# IOB-I2C-MCP23017.net
KiCad netlist of a schematic drawn in EAGLE
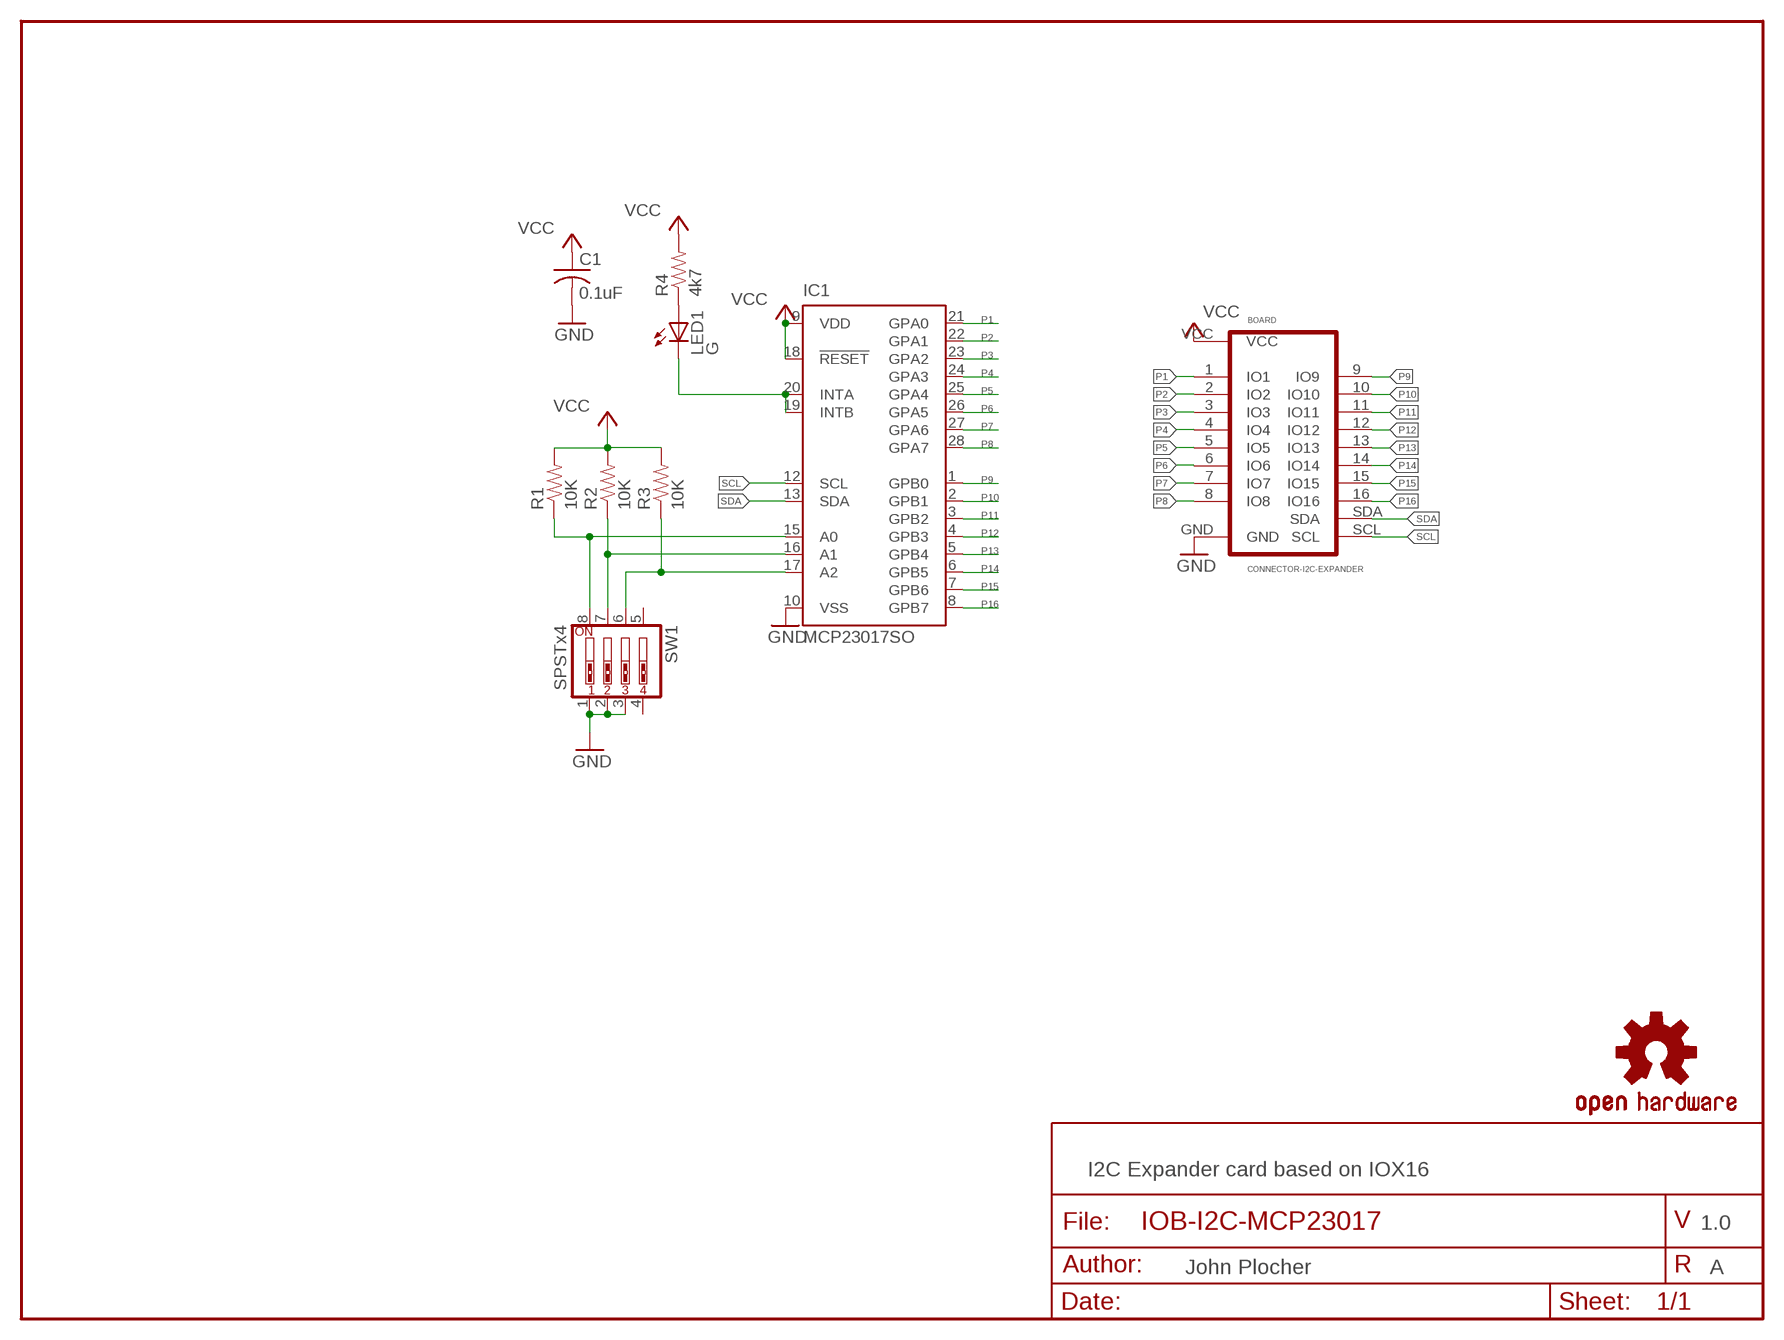
[diagram p0: schematic, sheet 1]

(export (version "E")
  (design (tool "Eeschema 10.0.6"))
  (components
    (comp (ref "BOARD")
      (value "CONNECTOR-I2C-EXPANDER")
      (footprint "eagle-import:I2C-EXPANDER")
      (libsource (lib "eagle-import") (part "CONNECTOR-I2C-EXPANDER"))
    )
    (comp (ref "C1")
      (value "0.1uF")
      (footprint "eagle-import:0603-CAP")
      (libsource (lib "eagle-import") (part "CAP0603"))
    )
    (comp (ref "IC1")
      (value "MCP23017SO")
      (footprint "eagle-import:SO28W")
      (fields (field (name "MF") "MICROCHIP") (field (name "MPN") "MCP23017-E/SO"))
      (libsource (lib "eagle-import") (part "MCP23017SO"))
    )
    (comp (ref "LED1")
      (value "G")
      (footprint "eagle-import:0603-LED")
      (libsource (lib "eagle-import") (part "LED0603-LED"))
    )
    (comp (ref "OSHW1")
      (value "OSHW")
      (footprint "eagle-import:OSHW-LOGO-M")
      (libsource (lib "eagle-import") (part "DOC-OSHW-LOGO-M"))
    )
    (comp (ref "R1")
      (value "10K")
      (footprint "eagle-import:0603-RES")
      (libsource (lib "eagle-import") (part "R0603-RES"))
    )
    (comp (ref "R2")
      (value "10K")
      (footprint "eagle-import:0603-RES")
      (libsource (lib "eagle-import") (part "R0603-RES"))
    )
    (comp (ref "R3")
      (value "10K")
      (footprint "eagle-import:0603-RES")
      (libsource (lib "eagle-import") (part "R0603-RES"))
    )
    (comp (ref "R4")
      (value "4k7")
      (footprint "eagle-import:0603-RES")
      (libsource (lib "eagle-import") (part "R0603-RES"))
    )
    (comp (ref "SW1")
      (value "SPSTx4")
      (footprint "eagle-import:EDG-04")
      (libsource (lib "eagle-import") (part "SW_DIP-4"))
    )
  )
  (nets
    (net (code "1") (name "GND") (class "Default")
      (node (ref "BOARD") (pin "GND") (pinfunction "GND_GND") (pintype "bidirectional"))
      (node (ref "C1") (pin "2") (pinfunction "2_2") (pintype "passive"))
      (node (ref "IC1") (pin "10") (pinfunction "VSS_10") (pintype "power_in"))
      (node (ref "SW1") (pin "1") (pinfunction "1_1") (pintype "passive"))
      (node (ref "SW1") (pin "2") (pinfunction "2_2") (pintype "passive"))
      (node (ref "SW1") (pin "3") (pinfunction "3_3") (pintype "passive"))
    )
    (net (code "2") (name "Net-(IC1-A0)") (class "Default")
      (node (ref "IC1") (pin "15") (pinfunction "A0_15") (pintype "input"))
      (node (ref "R1") (pin "1") (pinfunction "1_1") (pintype "passive"))
      (node (ref "SW1") (pin "8") (pinfunction "8_8") (pintype "passive"))
    )
    (net (code "3") (name "Net-(IC1-A1)") (class "Default")
      (node (ref "IC1") (pin "16") (pinfunction "A1_16") (pintype "input"))
      (node (ref "R2") (pin "1") (pinfunction "1_1") (pintype "passive"))
      (node (ref "SW1") (pin "7") (pinfunction "7_7") (pintype "passive"))
    )
    (net (code "4") (name "Net-(IC1-A2)") (class "Default")
      (node (ref "IC1") (pin "17") (pinfunction "A2_17") (pintype "input"))
      (node (ref "R3") (pin "1") (pinfunction "1_1") (pintype "passive"))
      (node (ref "SW1") (pin "6") (pinfunction "6_6") (pintype "passive"))
    )
    (net (code "5") (name "Net-(IC1-INTA)") (class "Default")
      (node (ref "IC1") (pin "19") (pinfunction "INTB_19") (pintype "output"))
      (node (ref "IC1") (pin "20") (pinfunction "INTA_20") (pintype "output"))
      (node (ref "LED1") (pin "C") (pinfunction "C_C") (pintype "passive"))
    )
    (net (code "6") (name "Net-(LED1-PadA)") (class "Default")
      (node (ref "LED1") (pin "A") (pinfunction "A_A") (pintype "passive"))
      (node (ref "R4") (pin "1") (pinfunction "1_1") (pintype "passive"))
    )
    (net (code "7") (name "P1") (class "Default")
      (node (ref "BOARD") (pin "1") (pinfunction "IO1_1") (pintype "bidirectional"))
      (node (ref "IC1") (pin "21") (pinfunction "GPA0_21") (pintype "bidirectional"))
    )
    (net (code "8") (name "P2") (class "Default")
      (node (ref "BOARD") (pin "2") (pinfunction "IO2_2") (pintype "bidirectional"))
      (node (ref "IC1") (pin "22") (pinfunction "GPA1_22") (pintype "bidirectional"))
    )
    (net (code "9") (name "P3") (class "Default")
      (node (ref "BOARD") (pin "3") (pinfunction "IO3_3") (pintype "bidirectional"))
      (node (ref "IC1") (pin "23") (pinfunction "GPA2_23") (pintype "bidirectional"))
    )
    (net (code "10") (name "P4") (class "Default")
      (node (ref "BOARD") (pin "4") (pinfunction "IO4_4") (pintype "bidirectional"))
      (node (ref "IC1") (pin "24") (pinfunction "GPA3_24") (pintype "bidirectional"))
    )
    (net (code "11") (name "P5") (class "Default")
      (node (ref "BOARD") (pin "5") (pinfunction "IO5_5") (pintype "bidirectional"))
      (node (ref "IC1") (pin "25") (pinfunction "GPA4_25") (pintype "bidirectional"))
    )
    (net (code "12") (name "P6") (class "Default")
      (node (ref "BOARD") (pin "6") (pinfunction "IO6_6") (pintype "bidirectional"))
      (node (ref "IC1") (pin "26") (pinfunction "GPA5_26") (pintype "bidirectional"))
    )
    (net (code "13") (name "P7") (class "Default")
      (node (ref "BOARD") (pin "7") (pinfunction "IO7_7") (pintype "bidirectional"))
      (node (ref "IC1") (pin "27") (pinfunction "GPA6_27") (pintype "bidirectional"))
    )
    (net (code "14") (name "P8") (class "Default")
      (node (ref "BOARD") (pin "8") (pinfunction "IO8_8") (pintype "bidirectional"))
      (node (ref "IC1") (pin "28") (pinfunction "GPA7_28") (pintype "bidirectional"))
    )
    (net (code "15") (name "P9") (class "Default")
      (node (ref "BOARD") (pin "9") (pinfunction "IO9_9") (pintype "bidirectional"))
      (node (ref "IC1") (pin "1") (pinfunction "GPB0_1") (pintype "bidirectional"))
    )
    (net (code "16") (name "P10") (class "Default")
      (node (ref "BOARD") (pin "10") (pinfunction "IO10_10") (pintype "bidirectional"))
      (node (ref "IC1") (pin "2") (pinfunction "GPB1_2") (pintype "bidirectional"))
    )
    (net (code "17") (name "P11") (class "Default")
      (node (ref "BOARD") (pin "11") (pinfunction "IO11_11") (pintype "bidirectional"))
      (node (ref "IC1") (pin "3") (pinfunction "GPB2_3") (pintype "bidirectional"))
    )
    (net (code "18") (name "P12") (class "Default")
      (node (ref "BOARD") (pin "12") (pinfunction "IO12_12") (pintype "bidirectional"))
      (node (ref "IC1") (pin "4") (pinfunction "GPB3_4") (pintype "bidirectional"))
    )
    (net (code "19") (name "P13") (class "Default")
      (node (ref "BOARD") (pin "13") (pinfunction "IO13_13") (pintype "bidirectional"))
      (node (ref "IC1") (pin "5") (pinfunction "GPB4_5") (pintype "bidirectional"))
    )
    (net (code "20") (name "P14") (class "Default")
      (node (ref "BOARD") (pin "14") (pinfunction "IO14_14") (pintype "bidirectional"))
      (node (ref "IC1") (pin "6") (pinfunction "GPB5_6") (pintype "bidirectional"))
    )
    (net (code "21") (name "P15") (class "Default")
      (node (ref "BOARD") (pin "15") (pinfunction "IO15_15") (pintype "bidirectional"))
      (node (ref "IC1") (pin "7") (pinfunction "GPB6_7") (pintype "bidirectional"))
    )
    (net (code "22") (name "P16") (class "Default")
      (node (ref "BOARD") (pin "16") (pinfunction "IO16_16") (pintype "bidirectional"))
      (node (ref "IC1") (pin "8") (pinfunction "GPB7_8") (pintype "bidirectional"))
    )
    (net (code "23") (name "SCL") (class "Default")
      (node (ref "BOARD") (pin "SCL") (pinfunction "SCL_SCL") (pintype "bidirectional"))
      (node (ref "IC1") (pin "12") (pinfunction "SCL_12") (pintype "input"))
    )
    (net (code "24") (name "SDA") (class "Default")
      (node (ref "BOARD") (pin "SDA") (pinfunction "SDA_SDA") (pintype "bidirectional"))
      (node (ref "IC1") (pin "13") (pinfunction "SDA_13") (pintype "bidirectional"))
    )
    (net (code "25") (name "VCC") (class "Default")
      (node (ref "BOARD") (pin "VCC") (pinfunction "VCC_VCC") (pintype "bidirectional"))
      (node (ref "C1") (pin "1") (pinfunction "1_1") (pintype "passive"))
      (node (ref "IC1") (pin "18") (pinfunction "~{RESET}_18") (pintype "input"))
      (node (ref "IC1") (pin "9") (pinfunction "VDD_9") (pintype "power_in"))
      (node (ref "R1") (pin "2") (pinfunction "2_2") (pintype "passive"))
      (node (ref "R2") (pin "2") (pinfunction "2_2") (pintype "passive"))
      (node (ref "R3") (pin "2") (pinfunction "2_2") (pintype "passive"))
      (node (ref "R4") (pin "2") (pinfunction "2_2") (pintype "passive"))
    )
    (net (code "26") (name "unconnected-(SW1-Pad4)") (class "Default")
      (node (ref "SW1") (pin "4") (pinfunction "4_4") (pintype "passive"))
    )
    (net (code "27") (name "unconnected-(SW1-Pad5)") (class "Default")
      (node (ref "SW1") (pin "5") (pinfunction "5_5") (pintype "passive"))
    )
  )
)
